# Controler.net
KiCad netlist of a schematic drawn in Altium Designer
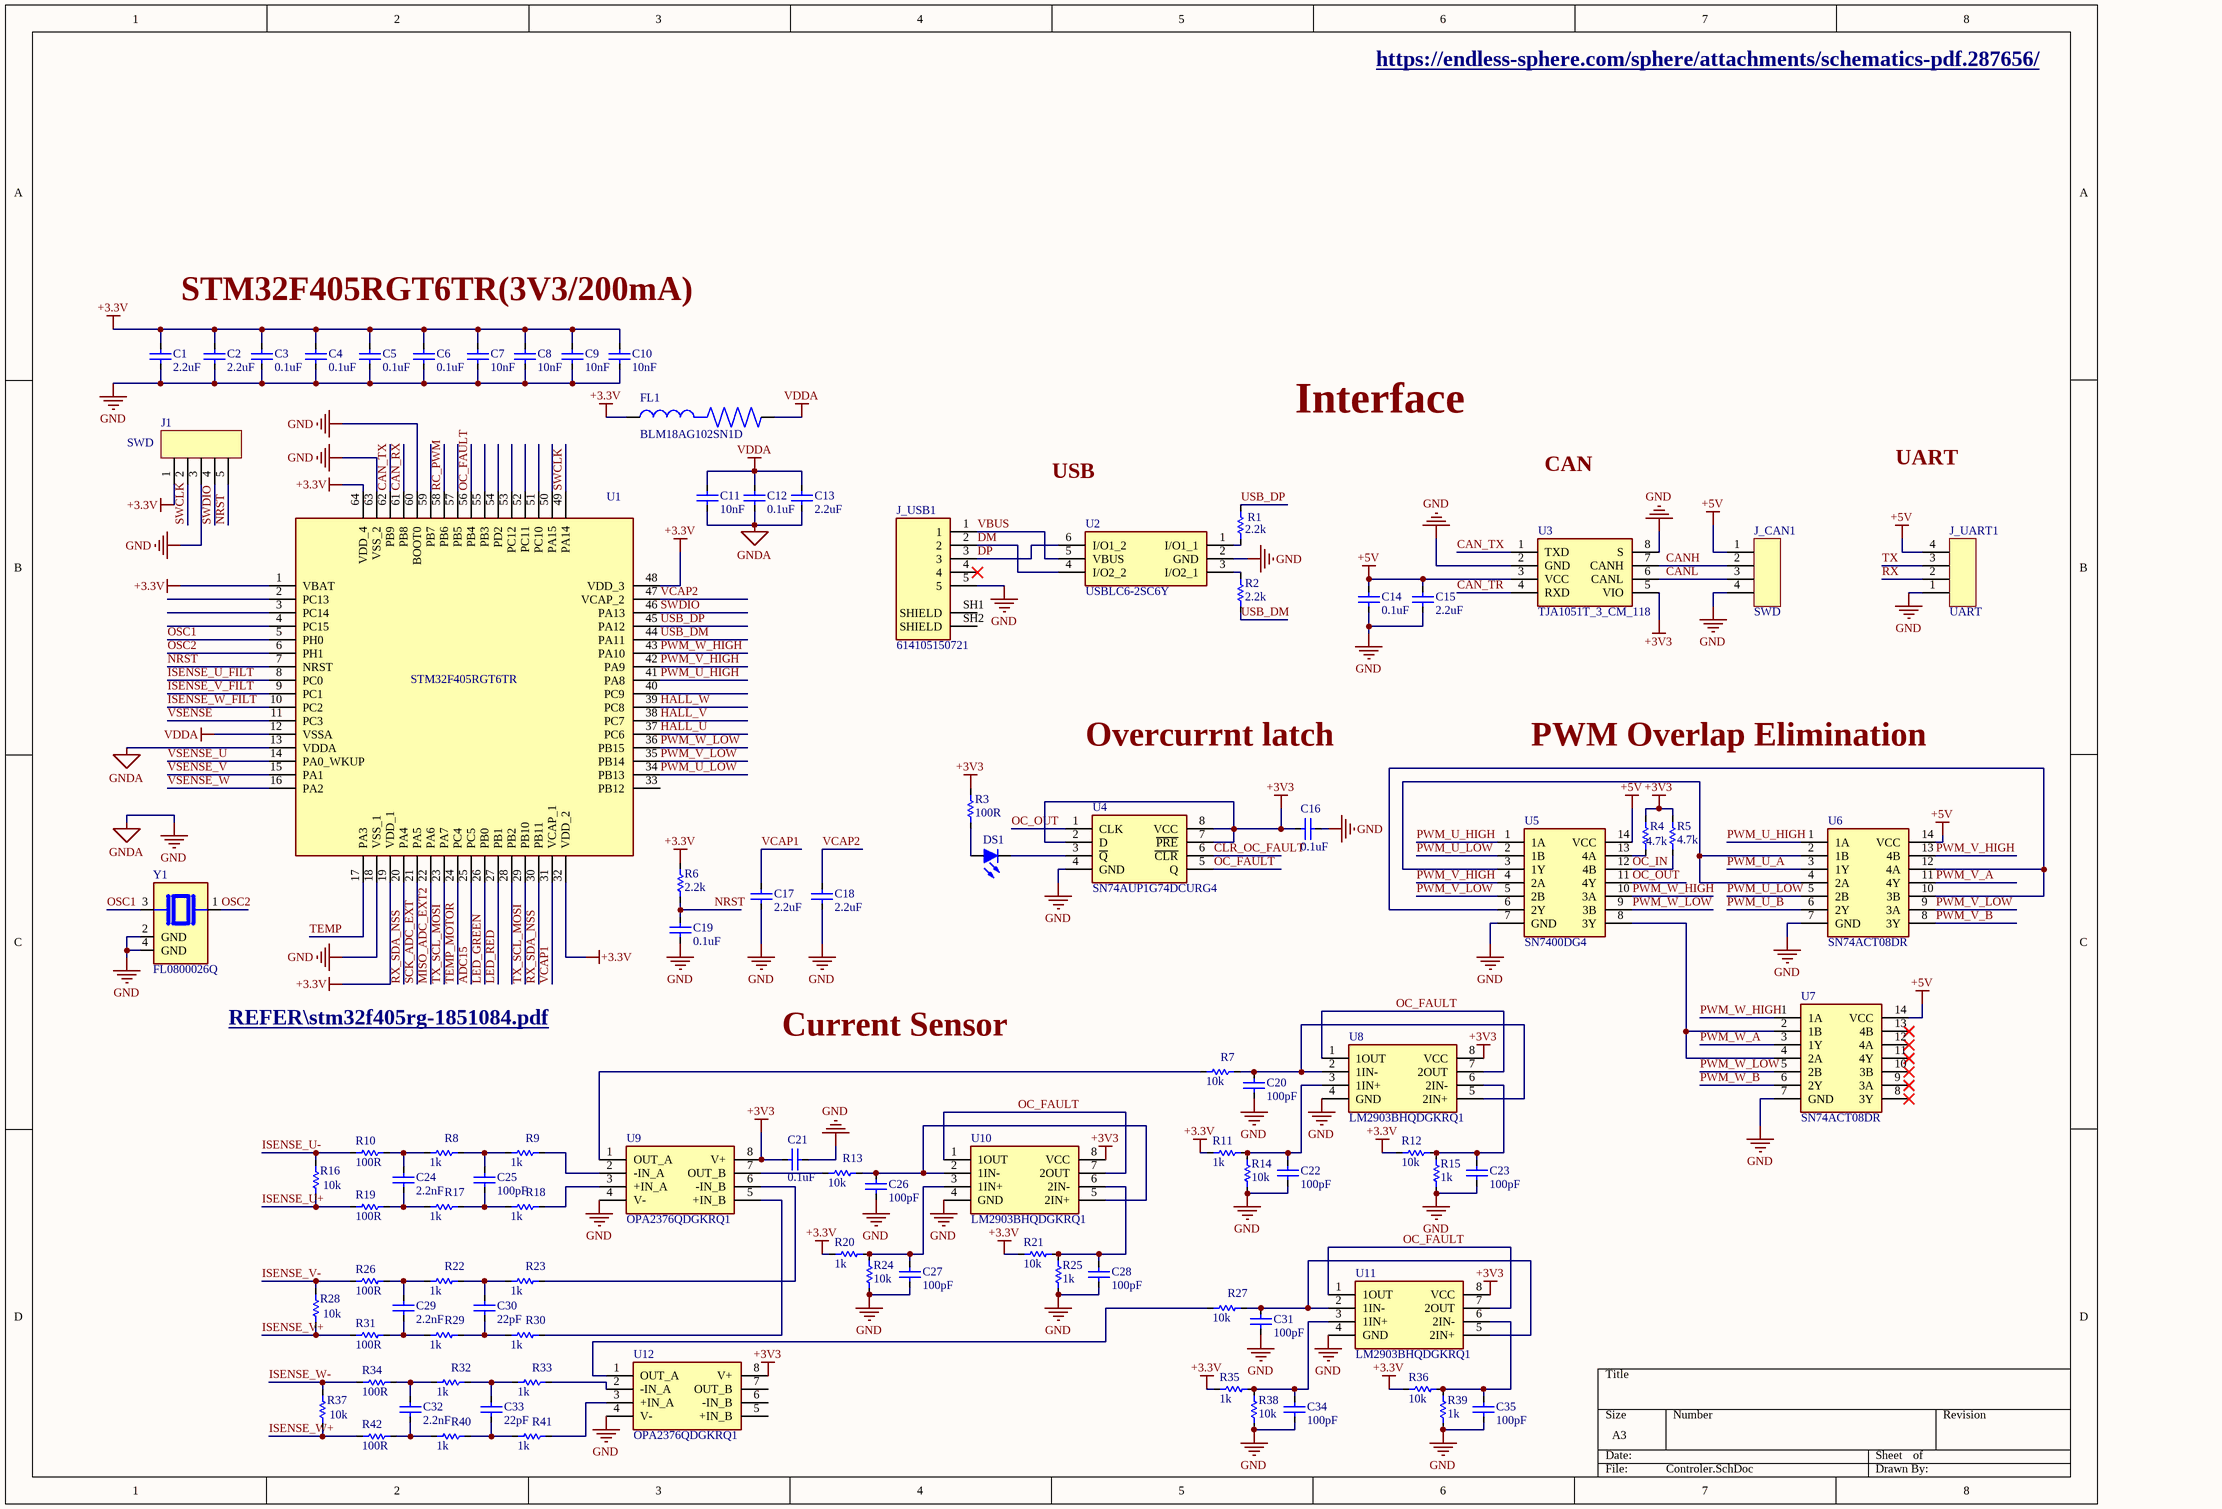
[diagram p0: Controler.SchDoc]

(export (version "E")
  (design (tool "Eeschema 10.0.6"))
  (components
    (comp (ref "C1")
      (value "2.2uF")
      (footprint "SMD_C(0603)")
      (description "PHE840MA6100MA04R17")
      (fields
        (field (name "MANUFACTURER") "Yageo")
        (field (name "MANUFACTURER PART NUMBER") "CC0603KPX7R9BB104")
      )
      (libsource (lib "CameraBoard") (part "Cap_9"))
    )
    (comp (ref "C2")
      (value "2.2uF")
      (footprint "SMD_C(0603)")
      (description "PHE840MA6100MA04R17")
      (fields
        (field (name "MANUFACTURER") "Yageo")
        (field (name "MANUFACTURER PART NUMBER") "CC0603KPX7R9BB104")
      )
      (libsource (lib "CameraBoard") (part "Cap_9"))
    )
    (comp (ref "C3")
      (value "0.1uF")
      (footprint "SMD_C(0402)")
      (description "Multilayer Ceramic Capacitors MLCC - SMD/SMT 50 V 0.1uF X7R 0603 10%")
      (fields
        (field (name "MANUFACTURER") "Yageo")
        (field (name "MANUFACTURER PART NUMBER") "CC0603KPX7R9BB104")
      )
      (libsource (lib "CameraBoard") (part "Cap_1"))
    )
    (comp (ref "C4")
      (value "0.1uF")
      (footprint "SMD_C(0402)")
      (description "Multilayer Ceramic Capacitors MLCC - SMD/SMT 50 V 0.1uF X7R 0603 10%")
      (fields
        (field (name "MANUFACTURER") "Yageo")
        (field (name "MANUFACTURER PART NUMBER") "CC0603KPX7R9BB104")
      )
      (libsource (lib "CameraBoard") (part "Cap_1"))
    )
    (comp (ref "C5")
      (value "0.1uF")
      (footprint "SMD_C(0402)")
      (description "Multilayer Ceramic Capacitors MLCC - SMD/SMT 50 V 0.1uF X7R 0603 10%")
      (fields
        (field (name "MANUFACTURER") "Yageo")
        (field (name "MANUFACTURER PART NUMBER") "CC0603KPX7R9BB104")
      )
      (libsource (lib "CameraBoard") (part "Cap_1"))
    )
    (comp (ref "C6")
      (value "0.1uF")
      (footprint "SMD_C(0402)")
      (description "Multilayer Ceramic Capacitors MLCC - SMD/SMT 50 V 0.1uF X7R 0603 10%")
      (fields
        (field (name "MANUFACTURER") "Yageo")
        (field (name "MANUFACTURER PART NUMBER") "CC0603KPX7R9BB104")
      )
      (libsource (lib "CameraBoard") (part "Cap_1"))
    )
    (comp (ref "C7")
      (value "10nF")
      (footprint "SMD_C(0402)")
      (description "Multilayer Ceramic Capacitors MLCC - SMD/SMT 50 V 10nF X7R 0603 10%")
      (fields
        (field (name "MANUFACTURER") "Yageo")
        (field (name "MANUFACTURER PART NUMBER") "CC0603KPX7R9BB103")
      )
      (libsource (lib "CameraBoard") (part "Cap_2"))
    )
    (comp (ref "C8")
      (value "10nF")
      (footprint "SMD_C(0402)")
      (description "Multilayer Ceramic Capacitors MLCC - SMD/SMT 50 V 10nF X7R 0603 10%")
      (fields
        (field (name "MANUFACTURER") "Yageo")
        (field (name "MANUFACTURER PART NUMBER") "CC0603KPX7R9BB103")
      )
      (libsource (lib "CameraBoard") (part "Cap_2"))
    )
    (comp (ref "C9")
      (value "10nF")
      (footprint "SMD_C(0402)")
      (description "Multilayer Ceramic Capacitors MLCC - SMD/SMT 50 V 10nF X7R 0603 10%")
      (fields
        (field (name "MANUFACTURER") "Yageo")
        (field (name "MANUFACTURER PART NUMBER") "CC0603KPX7R9BB103")
      )
      (libsource (lib "CameraBoard") (part "Cap_2"))
    )
    (comp (ref "C10")
      (value "10nF")
      (footprint "SMD_C(0402)")
      (description "Multilayer Ceramic Capacitors MLCC - SMD/SMT 50 V 10nF X7R 0603 10%")
      (fields
        (field (name "MANUFACTURER") "Yageo")
        (field (name "MANUFACTURER PART NUMBER") "CC0603KPX7R9BB103")
      )
      (libsource (lib "CameraBoard") (part "Cap_2"))
    )
    (comp (ref "C11")
      (value "10nF")
      (footprint "SMD_C(0402)")
      (description "Multilayer Ceramic Capacitors MLCC - SMD/SMT 50 V 10nF X7R 0603 10%")
      (fields
        (field (name "MANUFACTURER") "Yageo")
        (field (name "MANUFACTURER PART NUMBER") "CC0603KPX7R9BB103")
      )
      (libsource (lib "CameraBoard") (part "Cap_2"))
    )
    (comp (ref "C12")
      (value "0.1uF")
      (footprint "SMD_C(0402)")
      (description "Multilayer Ceramic Capacitors MLCC - SMD/SMT 50 V 0.1uF X7R 0603 10%")
      (fields
        (field (name "MANUFACTURER") "Yageo")
        (field (name "MANUFACTURER PART NUMBER") "CC0603KPX7R9BB104")
      )
      (libsource (lib "CameraBoard") (part "Cap_1"))
    )
    (comp (ref "C13")
      (value "2.2uF")
      (footprint "SMD_C(0603)")
      (description "PHE840MA6100MA04R17")
      (fields
        (field (name "MANUFACTURER") "Yageo")
        (field (name "MANUFACTURER PART NUMBER") "CC0603KPX7R9BB104")
      )
      (libsource (lib "CameraBoard") (part "Cap_9"))
    )
    (comp (ref "C14")
      (value "0.1uF")
      (footprint "SMD_C(0402)")
      (description "Multilayer Ceramic Capacitors MLCC - SMD/SMT 50 V 0.1uF X7R 0603 10%")
      (fields
        (field (name "MANUFACTURER") "Yageo")
        (field (name "MANUFACTURER PART NUMBER") "CC0603KPX7R9BB104")
      )
      (libsource (lib "CameraBoard") (part "Cap_1"))
    )
    (comp (ref "C15")
      (value "2.2uF")
      (footprint "SMD_C(0603)")
      (description "Multilayer Ceramic Capacitors MLCC - SMD/SMT 2.2 uF 50 VDC 10% 1206 X7R AEC-Q200")
      (fields
        (field (name "MANUFACTURER") "Yageo")
        (field (name "MANUFACTURER PART NUMBER") "GCM31CR71H225KA55K")
      )
      (libsource (lib "CameraBoard") (part "Cap_4"))
    )
    (comp (ref "C16")
      (value "0.1uF")
      (footprint "SMD_C(0402)")
      (description "Multilayer Ceramic Capacitors MLCC - SMD/SMT 50 V 0.1uF X7R 0603 10%")
      (fields
        (field (name "MANUFACTURER") "Yageo")
        (field (name "MANUFACTURER PART NUMBER") "CC0603KPX7R9BB104")
      )
      (libsource (lib "CameraBoard") (part "Cap_1"))
    )
    (comp (ref "C17")
      (value "2.2uF")
      (footprint "SMD_C(0603)")
      (description "Multilayer Ceramic Capacitors MLCC - SMD/SMT 2.2 uF 50 VDC 10% 1206 X7R AEC-Q200")
      (fields
        (field (name "MANUFACTURER") "Yageo")
        (field (name "MANUFACTURER PART NUMBER") "GCM31CR71H225KA55K")
      )
      (libsource (lib "CameraBoard") (part "Cap_4"))
    )
    (comp (ref "C18")
      (value "2.2uF")
      (footprint "SMD_C(0603)")
      (description "Multilayer Ceramic Capacitors MLCC - SMD/SMT 2.2 uF 50 VDC 10% 1206 X7R AEC-Q200")
      (fields
        (field (name "MANUFACTURER") "Yageo")
        (field (name "MANUFACTURER PART NUMBER") "GCM31CR71H225KA55K")
      )
      (libsource (lib "CameraBoard") (part "Cap_4"))
    )
    (comp (ref "C19")
      (value "0.1uF")
      (footprint "SMD_C(0402)")
      (description "Multilayer Ceramic Capacitors MLCC - SMD/SMT 50 V 0.1uF X7R 0603 10%")
      (fields
        (field (name "MANUFACTURER") "Yageo")
        (field (name "MANUFACTURER PART NUMBER") "CC0603KPX7R9BB104")
      )
      (libsource (lib "CameraBoard") (part "Cap_1"))
    )
    (comp (ref "C20")
      (value "100pF")
      (footprint "SMD_C(0402)")
      (description "PHE840MA6100MA04R17")
      (fields
        (field (name "MANUFACTURER") "Yageo")
        (field (name "MANUFACTURER PART NUMBER") "CC0603KPX7R9BB104")
      )
      (libsource (lib "CameraBoard") (part "Cap_7"))
    )
    (comp (ref "C21")
      (value "0.1uF")
      (footprint "SMD_C(0402)")
      (description "Multilayer Ceramic Capacitors MLCC - SMD/SMT 50 V 0.1uF X7R 0603 10%")
      (fields
        (field (name "MANUFACTURER") "Yageo")
        (field (name "MANUFACTURER PART NUMBER") "CC0603KPX7R9BB104")
      )
      (libsource (lib "CameraBoard") (part "Cap_1"))
    )
    (comp (ref "C22")
      (value "100pF")
      (footprint "SMD_C(0402)")
      (description "PHE840MA6100MA04R17")
      (fields
        (field (name "MANUFACTURER") "Yageo")
        (field (name "MANUFACTURER PART NUMBER") "CC0603KPX7R9BB104")
      )
      (libsource (lib "CameraBoard") (part "Cap_7"))
    )
    (comp (ref "C23")
      (value "100pF")
      (footprint "SMD_C(0402)")
      (description "PHE840MA6100MA04R17")
      (fields
        (field (name "MANUFACTURER") "Yageo")
        (field (name "MANUFACTURER PART NUMBER") "CC0603KPX7R9BB104")
      )
      (libsource (lib "CameraBoard") (part "Cap_7"))
    )
    (comp (ref "C24")
      (value "2.2nF")
      (footprint "SMD_C(0402)")
      (description "PHE840MA6100MA04R17")
      (fields
        (field (name "MANUFACTURER") "Yageo")
        (field (name "MANUFACTURER PART NUMBER") "CC0603KPX7R9BB104")
      )
      (libsource (lib "CameraBoard") (part "Cap_7"))
    )
    (comp (ref "C25")
      (value "100pF")
      (footprint "SMD_C(0402)")
      (description "PHE840MA6100MA04R17")
      (fields
        (field (name "MANUFACTURER") "Yageo")
        (field (name "MANUFACTURER PART NUMBER") "CC0603KPX7R9BB104")
      )
      (libsource (lib "CameraBoard") (part "Cap_7"))
    )
    (comp (ref "C26")
      (value "100pF")
      (footprint "SMD_C(0402)")
      (description "PHE840MA6100MA04R17")
      (fields
        (field (name "MANUFACTURER") "Yageo")
        (field (name "MANUFACTURER PART NUMBER") "CC0603KPX7R9BB104")
      )
      (libsource (lib "CameraBoard") (part "Cap_7"))
    )
    (comp (ref "C27")
      (value "100pF")
      (footprint "SMD_C(0402)")
      (description "PHE840MA6100MA04R17")
      (fields
        (field (name "MANUFACTURER") "Yageo")
        (field (name "MANUFACTURER PART NUMBER") "CC0603KPX7R9BB104")
      )
      (libsource (lib "CameraBoard") (part "Cap_7"))
    )
    (comp (ref "C28")
      (value "100pF")
      (footprint "SMD_C(0402)")
      (description "PHE840MA6100MA04R17")
      (fields
        (field (name "MANUFACTURER") "Yageo")
        (field (name "MANUFACTURER PART NUMBER") "CC0603KPX7R9BB104")
      )
      (libsource (lib "CameraBoard") (part "Cap_7"))
    )
    (comp (ref "C29")
      (value "2.2nF")
      (footprint "SMD_C(0402)")
      (description "PHE840MA6100MA04R17")
      (fields
        (field (name "MANUFACTURER") "Yageo")
        (field (name "MANUFACTURER PART NUMBER") "CC0603KPX7R9BB104")
      )
      (libsource (lib "CameraBoard") (part "Cap_7"))
    )
    (comp (ref "C30")
      (value "22pF")
      (footprint "SMD_C(0402)")
      (description "PHE840MA6100MA04R17")
      (fields
        (field (name "MANUFACTURER") "Yageo")
        (field (name "MANUFACTURER PART NUMBER") "CC0603KPX7R9BB104")
      )
      (libsource (lib "CameraBoard") (part "Cap_7"))
    )
    (comp (ref "C31")
      (value "100pF")
      (footprint "SMD_C(0402)")
      (description "PHE840MA6100MA04R17")
      (fields
        (field (name "MANUFACTURER") "Yageo")
        (field (name "MANUFACTURER PART NUMBER") "CC0603KPX7R9BB104")
      )
      (libsource (lib "CameraBoard") (part "Cap_7"))
    )
    (comp (ref "C32")
      (value "2.2nF")
      (footprint "SMD_C(0402)")
      (description "PHE840MA6100MA04R17")
      (fields
        (field (name "MANUFACTURER") "Yageo")
        (field (name "MANUFACTURER PART NUMBER") "CC0603KPX7R9BB104")
      )
      (libsource (lib "CameraBoard") (part "Cap_7"))
    )
    (comp (ref "C33")
      (value "22pF")
      (footprint "SMD_C(0402)")
      (description "PHE840MA6100MA04R17")
      (fields
        (field (name "MANUFACTURER") "Yageo")
        (field (name "MANUFACTURER PART NUMBER") "CC0603KPX7R9BB104")
      )
      (libsource (lib "CameraBoard") (part "Cap_7"))
    )
    (comp (ref "C34")
      (value "100pF")
      (footprint "SMD_C(0402)")
      (description "PHE840MA6100MA04R17")
      (fields
        (field (name "MANUFACTURER") "Yageo")
        (field (name "MANUFACTURER PART NUMBER") "CC0603KPX7R9BB104")
      )
      (libsource (lib "CameraBoard") (part "Cap_7"))
    )
    (comp (ref "C35")
      (value "100pF")
      (footprint "SMD_C(0402)")
      (description "PHE840MA6100MA04R17")
      (fields
        (field (name "MANUFACTURER") "Yageo")
        (field (name "MANUFACTURER PART NUMBER") "CC0603KPX7R9BB104")
      )
      (libsource (lib "CameraBoard") (part "Cap_7"))
    )
    (comp (ref "DS1")
      (value "SML-D12U1WT86")
      (footprint "LED0603")
      (description "Typical RED GaAs LED")
      (fields (field (name "MANUFACTURER") "Rohm Semiconductor"))
      (libsource (lib "Humidity Regulator") (part "SML-D12U1WT86"))
    )
    (comp (ref "FL1")
      (value "BLM18AG102SN1D")
      (footprint "BEADC1608X95N")
      (description "1 kOhms @ 100MHz 1 Ferrite Bead 0603 _1608 Metric_ 400mA 500mOhm")
      (fields (field (name "MF") "Murata") (field (name "DIGI-KEY_PART_NUMBER") "490-1015-1-ND"))
      (libsource (lib "BLM18AG102SN1D") (part "BLM18AG102SN1D"))
    )
    (comp (ref "J1")
      (value "SWD")
      (footprint "Header-2.54m-5pin")
      (description "5PinConnector")
      (libsource (lib "VESC_MotorController_3") (part "5PinConnector"))
    )
    (comp (ref "J_CAN1")
      (value "SWD")
      (footprint "Header-2.54m-4pin")
      (description "4PinConnector")
      (libsource (lib "CameraBoard") (part "4PinConnector"))
    )
    (comp (ref "J_UART1")
      (value "UART")
      (footprint "Header-2.54m-4pin")
      (description "4PinConnector")
      (libsource (lib "") (part "4PinConnector_1"))
    )
    (comp (ref "J_USB1")
      (value "614105150721")
      (footprint "WURTH_614105150721")
      (description "USB - micro B USB 2.0 Receptacle Connector 5 Position Through Hole")
      (fields (field (name "DIGI-KEY_PART_NUMBER") "732-5958-1-ND") (field (name "MF") "Wurth Electronics"))
      (libsource (lib "614105150721") (part "614105150721"))
    )
    (comp (ref "R1")
      (value "2.2k")
      (footprint "SMD_R(0402)")
      (description "CRCW04024R02FKED")
      (fields (field (name "PUBLISHER") "Altium Limited"))
      (libsource (lib "CameraBoard") (part "Res Semi_2"))
    )
    (comp (ref "R2")
      (value "2.2k")
      (footprint "SMD_R(0402)")
      (description "CRCW04024R02FKED")
      (fields (field (name "PUBLISHER") "Altium Limited"))
      (libsource (lib "CameraBoard") (part "Res Semi_2"))
    )
    (comp (ref "R3")
      (value "100R")
      (footprint "SMD_R(0402)")
      (description "CRCW04024R02FKED")
      (fields (field (name "PUBLISHER") "Altium Limited"))
      (libsource (lib "CameraBoard") (part "Res Semi_1"))
    )
    (comp (ref "R4")
      (value "4.7k")
      (footprint "SMD_R(0402)")
      (description "CRCW04024R02FKED")
      (fields (field (name "PUBLISHER") "Altium Limited"))
      (libsource (lib "CameraBoard") (part "Res Semi_3"))
    )
    (comp (ref "R5")
      (value "4.7k")
      (footprint "SMD_R(0402)")
      (description "CRCW04024R02FKED")
      (fields (field (name "PUBLISHER") "Altium Limited"))
      (libsource (lib "CameraBoard") (part "Res Semi_3"))
    )
    (comp (ref "R6")
      (value "2.2k")
      (footprint "SMD_R(0402)")
      (description "CRCW04024R02FKED")
      (fields (field (name "PUBLISHER") "Altium Limited"))
      (libsource (lib "CameraBoard") (part "Res Semi_2"))
    )
    (comp (ref "R7")
      (value "10k")
      (footprint "SMD_R(0402)")
      (description "CRCW04024R02FKED")
      (fields (field (name "PUBLISHER") "Altium Limited"))
      (libsource (lib "CameraBoard") (part "Res Semi_1"))
    )
    (comp (ref "R8")
      (value "1k")
      (footprint "SMD_R(0402)")
      (description "CRCW04024R02FKED")
      (fields (field (name "PUBLISHER") "Altium Limited"))
      (libsource (lib "CameraBoard") (part "Res Semi_1"))
    )
    (comp (ref "R9")
      (value "1k")
      (footprint "SMD_R(0402)")
      (description "CRCW04024R02FKED")
      (fields (field (name "PUBLISHER") "Altium Limited"))
      (libsource (lib "CameraBoard") (part "Res Semi_1"))
    )
    (comp (ref "R10")
      (value "100R")
      (footprint "SMD_R(0402)")
      (description "CRCW04024R02FKED")
      (fields (field (name "PUBLISHER") "Altium Limited"))
      (libsource (lib "CameraBoard") (part "Res Semi_1"))
    )
    (comp (ref "R11")
      (value "1k")
      (footprint "SMD_R(0402)")
      (description "CRCW04024R02FKED")
      (fields (field (name "PUBLISHER") "Altium Limited"))
      (libsource (lib "CameraBoard") (part "Res Semi_1"))
    )
    (comp (ref "R12")
      (value "10k")
      (footprint "SMD_R(0402)")
      (description "CRCW04024R02FKED")
      (fields (field (name "PUBLISHER") "Altium Limited"))
      (libsource (lib "CameraBoard") (part "Res Semi_1"))
    )
    (comp (ref "R13")
      (value "10k")
      (footprint "SMD_R(0402)")
      (description "CRCW04024R02FKED")
      (fields (field (name "PUBLISHER") "Altium Limited"))
      (libsource (lib "CameraBoard") (part "Res Semi_1"))
    )
    (comp (ref "R14")
      (value "10k")
      (footprint "SMD_R(0402)")
      (description "CRCW04024R02FKED")
      (fields (field (name "PUBLISHER") "Altium Limited"))
      (libsource (lib "CameraBoard") (part "Res Semi_1"))
    )
    (comp (ref "R15")
      (value "1k")
      (footprint "SMD_R(0402)")
      (description "CRCW04024R02FKED")
      (fields (field (name "PUBLISHER") "Altium Limited"))
      (libsource (lib "CameraBoard") (part "Res Semi_1"))
    )
    (comp (ref "R16")
      (value "10k")
      (footprint "SMD_R(0402)")
      (description "CRCW04024R02FKED")
      (fields (field (name "PUBLISHER") "Altium Limited"))
      (libsource (lib "CameraBoard") (part "Res Semi_1"))
    )
    (comp (ref "R17")
      (value "1k")
      (footprint "SMD_R(0402)")
      (description "CRCW04024R02FKED")
      (fields (field (name "PUBLISHER") "Altium Limited"))
      (libsource (lib "CameraBoard") (part "Res Semi_1"))
    )
    (comp (ref "R18")
      (value "1k")
      (footprint "SMD_R(0402)")
      (description "CRCW04024R02FKED")
      (fields (field (name "PUBLISHER") "Altium Limited"))
      (libsource (lib "CameraBoard") (part "Res Semi_1"))
    )
    (comp (ref "R19")
      (value "100R")
      (footprint "SMD_R(0402)")
      (description "CRCW04024R02FKED")
      (fields (field (name "PUBLISHER") "Altium Limited"))
      (libsource (lib "CameraBoard") (part "Res Semi_1"))
    )
    (comp (ref "R20")
      (value "1k")
      (footprint "SMD_R(0402)")
      (description "CRCW04024R02FKED")
      (fields (field (name "PUBLISHER") "Altium Limited"))
      (libsource (lib "CameraBoard") (part "Res Semi_1"))
    )
    (comp (ref "R21")
      (value "10k")
      (footprint "SMD_R(0402)")
      (description "CRCW04024R02FKED")
      (fields (field (name "PUBLISHER") "Altium Limited"))
      (libsource (lib "CameraBoard") (part "Res Semi_1"))
    )
    (comp (ref "R22")
      (value "1k")
      (footprint "SMD_R(0402)")
      (description "CRCW04024R02FKED")
      (fields (field (name "PUBLISHER") "Altium Limited"))
      (libsource (lib "CameraBoard") (part "Res Semi_1"))
    )
    (comp (ref "R23")
      (value "1k")
      (footprint "SMD_R(0402)")
      (description "CRCW04024R02FKED")
      (fields (field (name "PUBLISHER") "Altium Limited"))
      (libsource (lib "CameraBoard") (part "Res Semi_1"))
    )
    (comp (ref "R24")
      (value "10k")
      (footprint "SMD_R(0402)")
      (description "CRCW04024R02FKED")
      (fields (field (name "PUBLISHER") "Altium Limited"))
      (libsource (lib "CameraBoard") (part "Res Semi_1"))
    )
    (comp (ref "R25")
      (value "1k")
      (footprint "SMD_R(0402)")
      (description "CRCW04024R02FKED")
      (fields (field (name "PUBLISHER") "Altium Limited"))
      (libsource (lib "CameraBoard") (part "Res Semi_1"))
    )
    (comp (ref "R26")
      (value "100R")
      (footprint "SMD_R(0402)")
      (description "CRCW04024R02FKED")
      (fields (field (name "PUBLISHER") "Altium Limited"))
      (libsource (lib "CameraBoard") (part "Res Semi_1"))
    )
    (comp (ref "R27")
      (value "10k")
      (footprint "SMD_R(0402)")
      (description "CRCW04024R02FKED")
      (fields (field (name "PUBLISHER") "Altium Limited"))
      (libsource (lib "CameraBoard") (part "Res Semi_1"))
    )
    (comp (ref "R28")
      (value "10k")
      (footprint "SMD_R(0402)")
      (description "CRCW04024R02FKED")
      (fields (field (name "PUBLISHER") "Altium Limited"))
      (libsource (lib "CameraBoard") (part "Res Semi_1"))
    )
    (comp (ref "R29")
      (value "1k")
      (footprint "SMD_R(0402)")
      (description "CRCW04024R02FKED")
      (fields (field (name "PUBLISHER") "Altium Limited"))
      (libsource (lib "CameraBoard") (part "Res Semi_1"))
    )
    (comp (ref "R30")
      (value "1k")
      (footprint "SMD_R(0402)")
      (description "CRCW04024R02FKED")
      (fields (field (name "PUBLISHER") "Altium Limited"))
      (libsource (lib "CameraBoard") (part "Res Semi_1"))
    )
    (comp (ref "R31")
      (value "100R")
      (footprint "SMD_R(0402)")
      (description "CRCW04024R02FKED")
      (fields (field (name "PUBLISHER") "Altium Limited"))
      (libsource (lib "CameraBoard") (part "Res Semi_1"))
    )
    (comp (ref "R32")
      (value "1k")
      (footprint "SMD_R(0402)")
      (description "CRCW04024R02FKED")
      (fields (field (name "PUBLISHER") "Altium Limited"))
      (libsource (lib "CameraBoard") (part "Res Semi_1"))
    )
    (comp (ref "R33")
      (value "1k")
      (footprint "SMD_R(0402)")
      (description "CRCW04024R02FKED")
      (fields (field (name "PUBLISHER") "Altium Limited"))
      (libsource (lib "CameraBoard") (part "Res Semi_1"))
    )
    (comp (ref "R34")
      (value "100R")
      (footprint "SMD_R(0402)")
      (description "CRCW04024R02FKED")
      (fields (field (name "PUBLISHER") "Altium Limited"))
      (libsource (lib "CameraBoard") (part "Res Semi_1"))
    )
    (comp (ref "R35")
      (value "1k")
      (footprint "SMD_R(0402)")
      (description "CRCW04024R02FKED")
      (fields (field (name "PUBLISHER") "Altium Limited"))
      (libsource (lib "CameraBoard") (part "Res Semi_1"))
    )
    (comp (ref "R36")
      (value "10k")
      (footprint "SMD_R(0402)")
      (description "CRCW04024R02FKED")
      (fields (field (name "PUBLISHER") "Altium Limited"))
      (libsource (lib "CameraBoard") (part "Res Semi_1"))
    )
    (comp (ref "R37")
      (value "10k")
      (footprint "SMD_R(0402)")
      (description "CRCW04024R02FKED")
      (fields (field (name "PUBLISHER") "Altium Limited"))
      (libsource (lib "CameraBoard") (part "Res Semi_1"))
    )
    (comp (ref "R38")
      (value "10k")
      (footprint "SMD_R(0402)")
      (description "CRCW04024R02FKED")
      (fields (field (name "PUBLISHER") "Altium Limited"))
      (libsource (lib "CameraBoard") (part "Res Semi_1"))
    )
    (comp (ref "R39")
      (value "1k")
      (footprint "SMD_R(0402)")
      (description "CRCW04024R02FKED")
      (fields (field (name "PUBLISHER") "Altium Limited"))
      (libsource (lib "CameraBoard") (part "Res Semi_1"))
    )
    (comp (ref "R40")
      (value "1k")
      (footprint "SMD_R(0402)")
      (description "CRCW04024R02FKED")
      (fields (field (name "PUBLISHER") "Altium Limited"))
      (libsource (lib "CameraBoard") (part "Res Semi_1"))
    )
    (comp (ref "R41")
      (value "1k")
      (footprint "SMD_R(0402)")
      (description "CRCW04024R02FKED")
      (fields (field (name "PUBLISHER") "Altium Limited"))
      (libsource (lib "CameraBoard") (part "Res Semi_1"))
    )
    (comp (ref "R42")
      (value "100R")
      (footprint "SMD_R(0402)")
      (description "CRCW04024R02FKED")
      (fields (field (name "PUBLISHER") "Altium Limited"))
      (libsource (lib "CameraBoard") (part "Res Semi_1"))
    )
    (comp (ref "U1")
      (value "STM32F405RGT6TR")
      (footprint "QFP50P1200X1200X160-64N")
      (fields (field (name "MOUSER PART NUMBER") "511-STM32F405RGT6TR"))
      (libsource (lib "STM32F405RGT6TR") (part "STM32F405RGT6TR"))
    )
    (comp (ref "U2")
      (value "USBLC6-2SC6Y")
      (footprint "SOT95P280X145-6N")
      (fields (field (name "MOUSER PART NUMBER") "511-USBLC6-2SC6Y"))
      (libsource (lib "USBLC6-2SC6Y") (part "USBLC6-2SC6Y"))
    )
    (comp (ref "U3")
      (value "TJA1051T_3_CM_118")
      (footprint "SOIC127P600X175-8N")
      (description "CAN Interface IC BL Advanced Automotive Analog")
      (fields
        (field (name "MOUSER PART NUMBER") "771-TJA1051T/3CM118")
        (field (name "MANUFACTURER_PART_NUMBER") "TJA1051T/3/CM,118")
      )
      (libsource (lib "TJA1051T_3_CM_118") (part "TJA1051T_3_CM_118"))
    )
    (comp (ref "U4")
      (value "SN74AUP1G74DCURG4")
      (footprint "SOP50P310X90-8N")
      (description "Flip Flops Lo PWR SNGL Pos Edge Trgrd DType FlipFlop")
      (fields (field (name "MOUSER PART NUMBER") "595-74AUP1G74DCURG4"))
      (libsource (lib "SN74AUP1G74DCURG4") (part "SN74AUP1G74DCURG4"))
    )
    (comp (ref "U5")
      (value "SN7400DG4")
      (footprint "SOIC127P600X175-14N")
      (description "NAND Gate 4-Element 2-IN Bipolar 14-Pin SOIC Tube")
      (fields (field (name "MOUSER PART NUMBER") "595-SN7400DG4"))
      (libsource (lib "SN7400DG4") (part "SN7400DG4"))
    )
    (comp (ref "U6")
      (value "SN74ACT08DR")
      (footprint "SOIC127P600X175-14N")
      (description "Texas Instruments SN74ACT08DR, AND Quad 2 Input AND, 4.5  5.5 V, 14-Pin SOIC")
      (fields (field (name "MOUSER PART NUMBER") "595-SN74ACT08DR"))
      (libsource (lib "SN74ACT08DR") (part "SN74ACT08DR"))
    )
    (comp (ref "U7")
      (value "SN74ACT08DR")
      (footprint "SOIC127P600X175-14N")
      (description "Texas Instruments SN74ACT08DR, AND Quad 2 Input AND, 4.5  5.5 V, 14-Pin SOIC")
      (fields (field (name "MOUSER PART NUMBER") "595-SN74ACT08DR"))
      (libsource (lib "SN74ACT08DR") (part "SN74ACT08DR"))
    )
    (comp (ref "U8")
      (value "LM2903BHQDGKRQ1")
      (footprint "SOP65P490X110-8N")
      (description "Analog Comparators Automotive, dual, differential, commodity comparator")
      (fields (field (name "MOUSER PART NUMBER") "595-LM2903BHQDGKRQ1"))
      (libsource (lib "LM2903BHQDGKRQ1") (part "LM2903BHQDGKRQ1"))
    )
    (comp (ref "U9")
      (value "OPA2376QDGKRQ1")
      (footprint "SOP65P490X110-8N")
      (description "Low Noise, Low Quiescent Current, Precision Operational Amplifier e-trim/trade")
      (fields (field (name "MOUSER PART NUMBER") "595-OPA2376QDGKRQ1"))
      (libsource (lib "OPA2376QDGKRQ1") (part "OPA2376QDGKRQ1"))
    )
    (comp (ref "U10")
      (value "LM2903BHQDGKRQ1")
      (footprint "SOP65P490X110-8N")
      (description "Analog Comparators Automotive, dual, differential, commodity comparator")
      (fields (field (name "MOUSER PART NUMBER") "595-LM2903BHQDGKRQ1"))
      (libsource (lib "LM2903BHQDGKRQ1") (part "LM2903BHQDGKRQ1"))
    )
    (comp (ref "U11")
      (value "LM2903BHQDGKRQ1")
      (footprint "SOP65P490X110-8N")
      (description "Analog Comparators Automotive, dual, differential, commodity comparator")
      (fields (field (name "MOUSER PART NUMBER") "595-LM2903BHQDGKRQ1"))
      (libsource (lib "LM2903BHQDGKRQ1") (part "LM2903BHQDGKRQ1"))
    )
    (comp (ref "U12")
      (value "OPA2376QDGKRQ1")
      (footprint "SOP65P490X110-8N")
      (description "Low Noise, Low Quiescent Current, Precision Operational Amplifier e-trim/trade")
      (fields (field (name "MOUSER PART NUMBER") "595-OPA2376QDGKRQ1"))
      (libsource (lib "OPA2376QDGKRQ1") (part "OPA2376QDGKRQ1"))
    )
    (comp (ref "Y1")
      (value "FL0800026Q")
      (footprint "XTAL_FL0800026Q")
      (description "8 MHz Â±30ppm Crystal 8pF 400 Ohms 4-SMD, No Lead")
      (fields (field (name "MF") "Diodes Incorporated"))
      (libsource (lib "FL0800026Q") (part "FL0800026Q"))
    )
  )
  (nets
    (net (code "1") (name "+3.3V") (class "Default")
      (node (ref "C1") (pin "2") (pinfunction "2_2") (pintype "passive"))
      (node (ref "C10") (pin "2") (pinfunction "2_2") (pintype "passive"))
      (node (ref "C2") (pin "2") (pinfunction "2_2") (pintype "passive"))
      (node (ref "C3") (pin "2") (pinfunction "2_2") (pintype "passive"))
      (node (ref "C4") (pin "2") (pinfunction "2_2") (pintype "passive"))
      (node (ref "C5") (pin "2") (pinfunction "2_2") (pintype "passive"))
      (node (ref "C6") (pin "2") (pinfunction "2_2") (pintype "passive"))
      (node (ref "C7") (pin "2") (pinfunction "2_2") (pintype "passive"))
      (node (ref "C8") (pin "2") (pinfunction "2_2") (pintype "passive"))
      (node (ref "C9") (pin "2") (pinfunction "2_2") (pintype "passive"))
      (node (ref "FL1") (pin "1") (pinfunction "1_1") (pintype "passive"))
      (node (ref "J1") (pin "1") (pinfunction "1_1") (pintype "passive"))
      (node (ref "R11") (pin "1") (pinfunction "1_1") (pintype "passive"))
      (node (ref "R12") (pin "1") (pinfunction "1_1") (pintype "passive"))
      (node (ref "R20") (pin "1") (pinfunction "1_1") (pintype "passive"))
      (node (ref "R21") (pin "1") (pinfunction "1_1") (pintype "passive"))
      (node (ref "R35") (pin "1") (pinfunction "1_1") (pintype "passive"))
      (node (ref "R36") (pin "1") (pinfunction "1_1") (pintype "passive"))
      (node (ref "R6") (pin "2") (pinfunction "2_2") (pintype "passive"))
      (node (ref "U1") (pin "1") (pinfunction "VBAT_1") (pintype "passive"))
      (node (ref "U1") (pin "19") (pinfunction "VDD_1_19") (pintype "passive"))
      (node (ref "U1") (pin "32") (pinfunction "VDD_2_32") (pintype "passive"))
      (node (ref "U1") (pin "48") (pinfunction "VDD_3_48") (pintype "passive"))
      (node (ref "U1") (pin "64") (pinfunction "VDD_4_64") (pintype "passive"))
    )
    (net (code "2") (name "+3V3") (class "Default")
      (node (ref "C16") (pin "2") (pinfunction "2_2") (pintype "passive"))
      (node (ref "C21") (pin "1") (pinfunction "1_1") (pintype "passive"))
      (node (ref "R3") (pin "2") (pinfunction "2_2") (pintype "passive"))
      (node (ref "R4") (pin "2") (pinfunction "2_2") (pintype "passive"))
      (node (ref "R5") (pin "2") (pinfunction "2_2") (pintype "passive"))
      (node (ref "U10") (pin "8") (pinfunction "VCC_8") (pintype "passive"))
      (node (ref "U11") (pin "8") (pinfunction "VCC_8") (pintype "passive"))
      (node (ref "U12") (pin "8") (pinfunction "V+_8") (pintype "passive"))
      (node (ref "U3") (pin "5") (pinfunction "VIO_5") (pintype "passive"))
      (node (ref "U4") (pin "2") (pinfunction "D_2") (pintype "passive"))
      (node (ref "U4") (pin "7") (pinfunction "~{PRE}_7") (pintype "passive"))
      (node (ref "U4") (pin "8") (pinfunction "VCC_8") (pintype "passive"))
      (node (ref "U8") (pin "8") (pinfunction "VCC_8") (pintype "passive"))
      (node (ref "U9") (pin "8") (pinfunction "V+_8") (pintype "passive"))
    )
    (net (code "3") (name "+5V") (class "Default")
      (node (ref "C14") (pin "2") (pinfunction "2_2") (pintype "passive"))
      (node (ref "C15") (pin "2") (pinfunction "2_2") (pintype "passive"))
      (node (ref "J_CAN1") (pin "1") (pinfunction "1_1") (pintype "passive"))
      (node (ref "J_UART1") (pin "4") (pinfunction "4_4") (pintype "passive"))
      (node (ref "U3") (pin "3") (pinfunction "VCC_3") (pintype "power_in"))
      (node (ref "U5") (pin "14") (pinfunction "VCC_14") (pintype "passive"))
      (node (ref "U6") (pin "14") (pinfunction "VCC_14") (pintype "passive"))
      (node (ref "U7") (pin "14") (pinfunction "VCC_14") (pintype "passive"))
    )
    (net (code "4") (name "/ADC15") (class "Default")
      (node (ref "U1") (pin "25") (pinfunction "PC5_25") (pintype "passive"))
    )
    (net (code "5") (name "/CANH") (class "Default")
      (node (ref "J_CAN1") (pin "2") (pinfunction "2_2") (pintype "passive"))
      (node (ref "U3") (pin "7") (pinfunction "CANH_7") (pintype "passive"))
    )
    (net (code "6") (name "/CANL") (class "Default")
      (node (ref "J_CAN1") (pin "3") (pinfunction "3_3") (pintype "passive"))
      (node (ref "U3") (pin "6") (pinfunction "CANL_6") (pintype "passive"))
    )
    (net (code "7") (name "/CAN_RX") (class "Default")
      (node (ref "U1") (pin "61") (pinfunction "PB8_61") (pintype "passive"))
    )
    (net (code "8") (name "/CAN_TR") (class "Default")
      (node (ref "U3") (pin "4") (pinfunction "RXD_4") (pintype "passive"))
    )
    (net (code "9") (name "/CAN_TX") (class "Default")
      (node (ref "U1") (pin "62") (pinfunction "PB9_62") (pintype "passive"))
      (node (ref "U3") (pin "1") (pinfunction "TXD_1") (pintype "passive"))
    )
    (net (code "10") (name "/CLR_OC_FAULT") (class "Default")
      (node (ref "U4") (pin "6") (pinfunction "~{CLR}_6") (pintype "passive"))
    )
    (net (code "11") (name "/DM") (class "Default")
      (node (ref "J_USB1") (pin "2") (pinfunction "2_2") (pintype "passive"))
      (node (ref "U2") (pin "4") (pinfunction "I/O2_2_4") (pintype "passive"))
    )
    (net (code "12") (name "/DP") (class "Default")
      (node (ref "J_USB1") (pin "3") (pinfunction "3_3") (pintype "passive"))
      (node (ref "U2") (pin "6") (pinfunction "I/O1_2_6") (pintype "passive"))
    )
    (net (code "13") (name "/HALL_U") (class "Default")
      (node (ref "U1") (pin "37") (pinfunction "PC6_37") (pintype "passive"))
    )
    (net (code "14") (name "/HALL_V") (class "Default")
      (node (ref "U1") (pin "38") (pinfunction "PC7_38") (pintype "passive"))
    )
    (net (code "15") (name "/HALL_W") (class "Default")
      (node (ref "U1") (pin "39") (pinfunction "PC8_39") (pintype "passive"))
    )
    (net (code "16") (name "/ISENSE_U+") (class "Default")
      (node (ref "R16") (pin "2") (pinfunction "2_2") (pintype "passive"))
      (node (ref "R19") (pin "2") (pinfunction "2_2") (pintype "passive"))
    )
    (net (code "17") (name "/ISENSE_U-") (class "Default")
      (node (ref "R10") (pin "2") (pinfunction "2_2") (pintype "passive"))
      (node (ref "R16") (pin "1") (pinfunction "1_1") (pintype "passive"))
    )
    (net (code "18") (name "/ISENSE_U_FILT") (class "Default")
      (node (ref "U1") (pin "8") (pinfunction "PC0_8") (pintype "passive"))
    )
    (net (code "19") (name "/ISENSE_V+") (class "Default")
      (node (ref "R28") (pin "2") (pinfunction "2_2") (pintype "passive"))
      (node (ref "R31") (pin "2") (pinfunction "2_2") (pintype "passive"))
    )
    (net (code "20") (name "/ISENSE_V-") (class "Default")
      (node (ref "R26") (pin "2") (pinfunction "2_2") (pintype "passive"))
      (node (ref "R28") (pin "1") (pinfunction "1_1") (pintype "passive"))
    )
    (net (code "21") (name "/ISENSE_V_FILT") (class "Default")
      (node (ref "U1") (pin "9") (pinfunction "PC1_9") (pintype "passive"))
    )
    (net (code "22") (name "/ISENSE_W+") (class "Default")
      (node (ref "R37") (pin "2") (pinfunction "2_2") (pintype "passive"))
      (node (ref "R42") (pin "2") (pinfunction "2_2") (pintype "passive"))
    )
    (net (code "23") (name "/ISENSE_W-") (class "Default")
      (node (ref "R34") (pin "2") (pinfunction "2_2") (pintype "passive"))
      (node (ref "R37") (pin "1") (pinfunction "1_1") (pintype "passive"))
    )
    (net (code "24") (name "/ISENSE_W_FILT") (class "Default")
      (node (ref "U1") (pin "10") (pinfunction "PC2_10") (pintype "passive"))
    )
    (net (code "25") (name "/LED_GREEN") (class "Default")
      (node (ref "U1") (pin "26") (pinfunction "PB0_26") (pintype "passive"))
    )
    (net (code "26") (name "/LED_RED") (class "Default")
      (node (ref "U1") (pin "27") (pinfunction "PB1_27") (pintype "passive"))
    )
    (net (code "27") (name "/MISO_ADC_EXT2") (class "Default")
      (node (ref "U1") (pin "22") (pinfunction "PA6_22") (pintype "passive"))
    )
    (net (code "28") (name "/NRST") (class "Default")
      (node (ref "C19") (pin "2") (pinfunction "2_2") (pintype "passive"))
      (node (ref "J1") (pin "5") (pinfunction "5_5") (pintype "passive"))
      (node (ref "R6") (pin "1") (pinfunction "1_1") (pintype "passive"))
      (node (ref "U1") (pin "7") (pinfunction "NRST_7") (pintype "passive"))
    )
    (net (code "29") (name "/OC_FAULT") (class "Default")
      (node (ref "U1") (pin "56") (pinfunction "PB4_56") (pintype "passive"))
      (node (ref "U10") (pin "1") (pinfunction "1OUT_1") (pintype "passive"))
      (node (ref "U10") (pin "7") (pinfunction "2OUT_7") (pintype "passive"))
      (node (ref "U11") (pin "1") (pinfunction "1OUT_1") (pintype "passive"))
      (node (ref "U11") (pin "7") (pinfunction "2OUT_7") (pintype "passive"))
      (node (ref "U4") (pin "5") (pinfunction "Q_5") (pintype "passive"))
      (node (ref "U8") (pin "1") (pinfunction "1OUT_1") (pintype "passive"))
      (node (ref "U8") (pin "7") (pinfunction "2OUT_7") (pintype "passive"))
    )
    (net (code "30") (name "/OC_IN") (class "Default")
      (node (ref "R5") (pin "1") (pinfunction "1_1") (pintype "passive"))
      (node (ref "U5") (pin "12") (pinfunction "4B_12") (pintype "passive"))
    )
    (net (code "31") (name "/OC_OUT") (class "Default")
      (node (ref "U4") (pin "1") (pinfunction "CLK_1") (pintype "passive"))
      (node (ref "U5") (pin "11") (pinfunction "4Y_11") (pintype "passive"))
    )
    (net (code "32") (name "/OSC1") (class "Default")
      (node (ref "U1") (pin "5") (pinfunction "PH0_5") (pintype "passive"))
      (node (ref "Y1") (pin "3") (pinfunction "2_3") (pintype "passive"))
    )
    (net (code "33") (name "/OSC2") (class "Default")
      (node (ref "U1") (pin "6") (pinfunction "PH1_6") (pintype "passive"))
      (node (ref "Y1") (pin "1") (pinfunction "1_1") (pintype "passive"))
    )
    (net (code "34") (name "/PWM_U_A") (class "Default")
      (node (ref "U6") (pin "3") (pinfunction "1Y_3") (pintype "passive"))
    )
    (net (code "35") (name "/PWM_U_B") (class "Default")
      (node (ref "U6") (pin "6") (pinfunction "2Y_6") (pintype "passive"))
    )
    (net (code "36") (name "/PWM_U_HIGH") (class "Default")
      (node (ref "U1") (pin "41") (pinfunction "PA8_41") (pintype "passive"))
      (node (ref "U5") (pin "1") (pinfunction "1A_1") (pintype "passive"))
      (node (ref "U6") (pin "1") (pinfunction "1A_1") (pintype "passive"))
    )
    (net (code "37") (name "/PWM_U_LOW") (class "Default")
      (node (ref "U1") (pin "34") (pinfunction "PB13_34") (pintype "passive"))
      (node (ref "U5") (pin "2") (pinfunction "1B_2") (pintype "passive"))
      (node (ref "U6") (pin "5") (pinfunction "2B_5") (pintype "passive"))
    )
    (net (code "38") (name "/PWM_V_A") (class "Default")
      (node (ref "U6") (pin "11") (pinfunction "4Y_11") (pintype "passive"))
    )
    (net (code "39") (name "/PWM_V_B") (class "Default")
      (node (ref "U6") (pin "8") (pinfunction "3Y_8") (pintype "passive"))
    )
    (net (code "40") (name "/PWM_V_HIGH") (class "Default")
      (node (ref "U1") (pin "42") (pinfunction "PA9_42") (pintype "passive"))
      (node (ref "U5") (pin "4") (pinfunction "2A_4") (pintype "passive"))
      (node (ref "U6") (pin "13") (pinfunction "4B_13") (pintype "passive"))
    )
    (net (code "41") (name "/PWM_V_LOW") (class "Default")
      (node (ref "U1") (pin "35") (pinfunction "PB14_35") (pintype "passive"))
      (node (ref "U5") (pin "5") (pinfunction "2B_5") (pintype "passive"))
      (node (ref "U6") (pin "9") (pinfunction "3A_9") (pintype "passive"))
    )
    (net (code "42") (name "/PWM_W_A") (class "Default")
      (node (ref "U7") (pin "3") (pinfunction "1Y_3") (pintype "passive"))
    )
    (net (code "43") (name "/PWM_W_B") (class "Default")
      (node (ref "U7") (pin "6") (pinfunction "2Y_6") (pintype "passive"))
    )
    (net (code "44") (name "/PWM_W_HIGH") (class "Default")
      (node (ref "U1") (pin "43") (pinfunction "PA10_43") (pintype "passive"))
      (node (ref "U5") (pin "10") (pinfunction "3A_10") (pintype "passive"))
      (node (ref "U7") (pin "1") (pinfunction "1A_1") (pintype "passive"))
    )
    (net (code "45") (name "/PWM_W_LOW") (class "Default")
      (node (ref "U1") (pin "36") (pinfunction "PB15_36") (pintype "passive"))
      (node (ref "U5") (pin "9") (pinfunction "3B_9") (pintype "passive"))
      (node (ref "U7") (pin "5") (pinfunction "2B_5") (pintype "passive"))
    )
    (net (code "46") (name "/RC_PWM") (class "Default")
      (node (ref "U1") (pin "58") (pinfunction "PB6_58") (pintype "passive"))
    )
    (net (code "47") (name "/RX") (class "Default")
      (node (ref "J_UART1") (pin "2") (pinfunction "2_2") (pintype "passive"))
    )
    (net (code "48") (name "/RX_SDA_NSS") (class "Default")
      (node (ref "U1") (pin "20") (pinfunction "PA4_20") (pintype "passive"))
      (node (ref "U1") (pin "30") (pinfunction "PB11_30") (pintype "passive"))
    )
    (net (code "49") (name "/SCK_ADC_EXT") (class "Default")
      (node (ref "U1") (pin "21") (pinfunction "PA5_21") (pintype "passive"))
    )
    (net (code "50") (name "/SWCLK") (class "Default")
      (node (ref "J1") (pin "2") (pinfunction "2_2") (pintype "passive"))
      (node (ref "U1") (pin "49") (pinfunction "PA14_49") (pintype "passive"))
    )
    (net (code "51") (name "/SWDIO") (class "Default")
      (node (ref "J1") (pin "4") (pinfunction "4_4") (pintype "passive"))
      (node (ref "U1") (pin "46") (pinfunction "PA13_46") (pintype "passive"))
    )
    (net (code "52") (name "/TEMP") (class "Default")
      (node (ref "U1") (pin "17") (pinfunction "PA3_17") (pintype "passive"))
    )
    (net (code "53") (name "/TEMP_MOTOR") (class "Default")
      (node (ref "U1") (pin "24") (pinfunction "PC4_24") (pintype "passive"))
    )
    (net (code "54") (name "/TX") (class "Default")
      (node (ref "J_UART1") (pin "3") (pinfunction "3_3") (pintype "passive"))
    )
    (net (code "55") (name "/TX_SCL_MOSI") (class "Default")
      (node (ref "U1") (pin "23") (pinfunction "PA7_23") (pintype "passive"))
      (node (ref "U1") (pin "29") (pinfunction "PB10_29") (pintype "passive"))
    )
    (net (code "56") (name "/USB_DM") (class "Default")
      (node (ref "R2") (pin "2") (pinfunction "2_2") (pintype "passive"))
      (node (ref "U1") (pin "44") (pinfunction "PA11_44") (pintype "passive"))
    )
    (net (code "57") (name "/USB_DP") (class "Default")
      (node (ref "R1") (pin "2") (pinfunction "2_2") (pintype "passive"))
      (node (ref "U1") (pin "45") (pinfunction "PA12_45") (pintype "passive"))
    )
    (net (code "58") (name "/VBUS") (class "Default")
      (node (ref "J_USB1") (pin "1") (pinfunction "1_1") (pintype "passive"))
      (node (ref "U2") (pin "5") (pinfunction "VBUS_5") (pintype "passive"))
    )
    (net (code "59") (name "/VCAP1") (class "Default")
      (node (ref "C17") (pin "2") (pinfunction "2_2") (pintype "passive"))
      (node (ref "U1") (pin "31") (pinfunction "VCAP_1_31") (pintype "passive"))
    )
    (net (code "60") (name "/VCAP2") (class "Default")
      (node (ref "C18") (pin "2") (pinfunction "2_2") (pintype "passive"))
      (node (ref "U1") (pin "47") (pinfunction "VCAP_2_47") (pintype "passive"))
    )
    (net (code "61") (name "/VSENSE") (class "Default")
      (node (ref "U1") (pin "11") (pinfunction "PC3_11") (pintype "passive"))
    )
    (net (code "62") (name "/VSENSE_U") (class "Default")
      (node (ref "U1") (pin "14") (pinfunction "PA0_WKUP_14") (pintype "passive"))
    )
    (net (code "63") (name "/VSENSE_V") (class "Default")
      (node (ref "U1") (pin "15") (pinfunction "PA1_15") (pintype "passive"))
    )
    (net (code "64") (name "/VSENSE_W") (class "Default")
      (node (ref "U1") (pin "16") (pinfunction "PA2_16") (pintype "passive"))
    )
    (net (code "65") (name "GND") (class "Default")
      (node (ref "C1") (pin "1") (pinfunction "1_1") (pintype "passive"))
      (node (ref "C10") (pin "1") (pinfunction "1_1") (pintype "passive"))
      (node (ref "C11") (pin "1") (pinfunction "1_1") (pintype "passive"))
      (node (ref "C12") (pin "1") (pinfunction "1_1") (pintype "passive"))
      (node (ref "C13") (pin "1") (pinfunction "1_1") (pintype "passive"))
      (node (ref "C14") (pin "1") (pinfunction "1_1") (pintype "passive"))
      (node (ref "C15") (pin "1") (pinfunction "1_1") (pintype "passive"))
      (node (ref "C16") (pin "1") (pinfunction "1_1") (pintype "passive"))
      (node (ref "C17") (pin "1") (pinfunction "1_1") (pintype "passive"))
      (node (ref "C18") (pin "1") (pinfunction "1_1") (pintype "passive"))
      (node (ref "C19") (pin "1") (pinfunction "1_1") (pintype "passive"))
      (node (ref "C2") (pin "1") (pinfunction "1_1") (pintype "passive"))
      (node (ref "C20") (pin "1") (pinfunction "1_1") (pintype "passive"))
      (node (ref "C21") (pin "2") (pinfunction "2_2") (pintype "passive"))
      (node (ref "C22") (pin "1") (pinfunction "1_1") (pintype "passive"))
      (node (ref "C23") (pin "1") (pinfunction "1_1") (pintype "passive"))
      (node (ref "C26") (pin "1") (pinfunction "1_1") (pintype "passive"))
      (node (ref "C27") (pin "1") (pinfunction "1_1") (pintype "passive"))
      (node (ref "C28") (pin "1") (pinfunction "1_1") (pintype "passive"))
      (node (ref "C3") (pin "1") (pinfunction "1_1") (pintype "passive"))
      (node (ref "C31") (pin "1") (pinfunction "1_1") (pintype "passive"))
      (node (ref "C34") (pin "1") (pinfunction "1_1") (pintype "passive"))
      (node (ref "C35") (pin "1") (pinfunction "1_1") (pintype "passive"))
      (node (ref "C4") (pin "1") (pinfunction "1_1") (pintype "passive"))
      (node (ref "C5") (pin "1") (pinfunction "1_1") (pintype "passive"))
      (node (ref "C6") (pin "1") (pinfunction "1_1") (pintype "passive"))
      (node (ref "C7") (pin "1") (pinfunction "1_1") (pintype "passive"))
      (node (ref "C8") (pin "1") (pinfunction "1_1") (pintype "passive"))
      (node (ref "C9") (pin "1") (pinfunction "1_1") (pintype "passive"))
      (node (ref "J1") (pin "3") (pinfunction "3_3") (pintype "passive"))
      (node (ref "J_CAN1") (pin "4") (pinfunction "4_4") (pintype "passive"))
      (node (ref "J_UART1") (pin "1") (pinfunction "1_1") (pintype "passive"))
      (node (ref "J_USB1") (pin "5") (pinfunction "5_5") (pintype "passive"))
      (node (ref "R14") (pin "2") (pinfunction "2_2") (pintype "passive"))
      (node (ref "R15") (pin "2") (pinfunction "2_2") (pintype "passive"))
      (node (ref "R24") (pin "2") (pinfunction "2_2") (pintype "passive"))
      (node (ref "R25") (pin "2") (pinfunction "2_2") (pintype "passive"))
      (node (ref "R38") (pin "2") (pinfunction "2_2") (pintype "passive"))
      (node (ref "R39") (pin "2") (pinfunction "2_2") (pintype "passive"))
      (node (ref "U1") (pin "13") (pinfunction "VDDA_13") (pintype "passive"))
      (node (ref "U1") (pin "18") (pinfunction "VSS_1_18") (pintype "passive"))
      (node (ref "U1") (pin "60") (pinfunction "BOOT0_60") (pintype "passive"))
      (node (ref "U1") (pin "63") (pinfunction "VSS_2_63") (pintype "passive"))
      (node (ref "U10") (pin "4") (pinfunction "GND_4") (pintype "passive"))
      (node (ref "U11") (pin "4") (pinfunction "GND_4") (pintype "passive"))
      (node (ref "U12") (pin "4") (pinfunction "V-_4") (pintype "passive"))
      (node (ref "U2") (pin "2") (pinfunction "GND_2") (pintype "passive"))
      (node (ref "U3") (pin "2") (pinfunction "GND_2") (pintype "passive"))
      (node (ref "U3") (pin "8") (pinfunction "S_8") (pintype "passive"))
      (node (ref "U4") (pin "4") (pinfunction "GND_4") (pintype "passive"))
      (node (ref "U5") (pin "7") (pinfunction "GND_7") (pintype "passive"))
      (node (ref "U6") (pin "7") (pinfunction "GND_7") (pintype "passive"))
      (node (ref "U7") (pin "7") (pinfunction "GND_7") (pintype "passive"))
      (node (ref "U8") (pin "4") (pinfunction "GND_4") (pintype "passive"))
      (node (ref "U9") (pin "4") (pinfunction "V-_4") (pintype "passive"))
      (node (ref "Y1") (pin "2") (pinfunction "GND_2") (pintype "power_in"))
      (node (ref "Y1") (pin "4") (pinfunction "GND_4") (pintype "power_in"))
    )
    (net (code "66") (name "Net-(C24-Pad1)") (class "Default")
      (node (ref "C24") (pin "1") (pinfunction "1_1") (pintype "passive"))
      (node (ref "R17") (pin "2") (pinfunction "2_2") (pintype "passive"))
      (node (ref "R19") (pin "1") (pinfunction "1_1") (pintype "passive"))
    )
    (net (code "67") (name "Net-(C24-Pad2)") (class "Default")
      (node (ref "C24") (pin "2") (pinfunction "2_2") (pintype "passive"))
      (node (ref "R10") (pin "1") (pinfunction "1_1") (pintype "passive"))
      (node (ref "R8") (pin "2") (pinfunction "2_2") (pintype "passive"))
    )
    (net (code "68") (name "Net-(C25-Pad1)") (class "Default")
      (node (ref "C25") (pin "1") (pinfunction "1_1") (pintype "passive"))
      (node (ref "R17") (pin "1") (pinfunction "1_1") (pintype "passive"))
      (node (ref "R18") (pin "2") (pinfunction "2_2") (pintype "passive"))
    )
    (net (code "69") (name "Net-(C25-Pad2)") (class "Default")
      (node (ref "C25") (pin "2") (pinfunction "2_2") (pintype "passive"))
      (node (ref "R8") (pin "1") (pinfunction "1_1") (pintype "passive"))
      (node (ref "R9") (pin "2") (pinfunction "2_2") (pintype "passive"))
    )
    (net (code "70") (name "Net-(C29-Pad1)") (class "Default")
      (node (ref "C29") (pin "1") (pinfunction "1_1") (pintype "passive"))
      (node (ref "R29") (pin "2") (pinfunction "2_2") (pintype "passive"))
      (node (ref "R31") (pin "1") (pinfunction "1_1") (pintype "passive"))
    )
    (net (code "71") (name "Net-(C29-Pad2)") (class "Default")
      (node (ref "C29") (pin "2") (pinfunction "2_2") (pintype "passive"))
      (node (ref "R22") (pin "2") (pinfunction "2_2") (pintype "passive"))
      (node (ref "R26") (pin "1") (pinfunction "1_1") (pintype "passive"))
    )
    (net (code "72") (name "Net-(C30-Pad1)") (class "Default")
      (node (ref "C30") (pin "1") (pinfunction "1_1") (pintype "passive"))
      (node (ref "R29") (pin "1") (pinfunction "1_1") (pintype "passive"))
      (node (ref "R30") (pin "2") (pinfunction "2_2") (pintype "passive"))
    )
    (net (code "73") (name "Net-(C30-Pad2)") (class "Default")
      (node (ref "C30") (pin "2") (pinfunction "2_2") (pintype "passive"))
      (node (ref "R22") (pin "1") (pinfunction "1_1") (pintype "passive"))
      (node (ref "R23") (pin "2") (pinfunction "2_2") (pintype "passive"))
    )
    (net (code "74") (name "Net-(C32-Pad1)") (class "Default")
      (node (ref "C32") (pin "1") (pinfunction "1_1") (pintype "passive"))
      (node (ref "R40") (pin "2") (pinfunction "2_2") (pintype "passive"))
      (node (ref "R42") (pin "1") (pinfunction "1_1") (pintype "passive"))
    )
    (net (code "75") (name "Net-(C32-Pad2)") (class "Default")
      (node (ref "C32") (pin "2") (pinfunction "2_2") (pintype "passive"))
      (node (ref "R32") (pin "2") (pinfunction "2_2") (pintype "passive"))
      (node (ref "R34") (pin "1") (pinfunction "1_1") (pintype "passive"))
    )
    (net (code "76") (name "Net-(C33-Pad1)") (class "Default")
      (node (ref "C33") (pin "1") (pinfunction "1_1") (pintype "passive"))
      (node (ref "R40") (pin "1") (pinfunction "1_1") (pintype "passive"))
      (node (ref "R41") (pin "2") (pinfunction "2_2") (pintype "passive"))
    )
    (net (code "77") (name "Net-(C33-Pad2)") (class "Default")
      (node (ref "C33") (pin "2") (pinfunction "2_2") (pintype "passive"))
      (node (ref "R32") (pin "1") (pinfunction "1_1") (pintype "passive"))
      (node (ref "R33") (pin "2") (pinfunction "2_2") (pintype "passive"))
    )
    (net (code "78") (name "Net-(DS1-PadA)") (class "Default")
      (node (ref "DS1") (pin "A") (pinfunction "A_A") (pintype "passive"))
      (node (ref "R3") (pin "1") (pinfunction "1_1") (pintype "passive"))
    )
    (net (code "79") (name "Net-(U2-I{slash}O1_1)") (class "Default")
      (node (ref "R1") (pin "1") (pinfunction "1_1") (pintype "passive"))
      (node (ref "U2") (pin "1") (pinfunction "I/O1_1_1") (pintype "passive"))
    )
    (net (code "80") (name "Net-(U2-I{slash}O2_1)") (class "Default")
      (node (ref "R2") (pin "1") (pinfunction "1_1") (pintype "passive"))
      (node (ref "U2") (pin "3") (pinfunction "I/O2_1_3") (pintype "passive"))
    )
    (net (code "81") (name "Net-(U4-~{Q})") (class "Default")
      (node (ref "DS1") (pin "C") (pinfunction "C_C") (pintype "passive"))
      (node (ref "U4") (pin "3") (pinfunction "~{Q}_3") (pintype "passive"))
    )
    (net (code "82") (name "Net-(U5-1Y)") (class "Default")
      (node (ref "U5") (pin "3") (pinfunction "1Y_3") (pintype "passive"))
      (node (ref "U6") (pin "2") (pinfunction "1B_2") (pintype "passive"))
      (node (ref "U6") (pin "4") (pinfunction "2A_4") (pintype "passive"))
    )
    (net (code "83") (name "Net-(U5-2Y)") (class "Default")
      (node (ref "U5") (pin "6") (pinfunction "2Y_6") (pintype "passive"))
      (node (ref "U6") (pin "10") (pinfunction "3B_10") (pintype "passive"))
      (node (ref "U6") (pin "12") (pinfunction "4A_12") (pintype "passive"))
    )
    (net (code "84") (name "Net-(U5-3Y)") (class "Default")
      (node (ref "U5") (pin "8") (pinfunction "3Y_8") (pintype "passive"))
      (node (ref "U7") (pin "2") (pinfunction "1B_2") (pintype "passive"))
      (node (ref "U7") (pin "4") (pinfunction "2A_4") (pintype "passive"))
    )
    (net (code "85") (name "Net-(U5-4A)") (class "Default")
      (node (ref "R4") (pin "1") (pinfunction "1_1") (pintype "passive"))
      (node (ref "U5") (pin "13") (pinfunction "4A_13") (pintype "passive"))
    )
    (net (code "86") (name "Net-(U8-1IN+)") (class "Default")
      (node (ref "C22") (pin "2") (pinfunction "2_2") (pintype "passive"))
      (node (ref "R11") (pin "2") (pinfunction "2_2") (pintype "passive"))
      (node (ref "R14") (pin "1") (pinfunction "1_1") (pintype "passive"))
      (node (ref "U8") (pin "3") (pinfunction "1IN+_3") (pintype "passive"))
    )
    (net (code "87") (name "Net-(U8-1IN-)") (class "Default")
      (node (ref "C20") (pin "2") (pinfunction "2_2") (pintype "passive"))
      (node (ref "R7") (pin "1") (pinfunction "1_1") (pintype "passive"))
      (node (ref "U8") (pin "2") (pinfunction "1IN-_2") (pintype "passive"))
      (node (ref "U8") (pin "5") (pinfunction "2IN+_5") (pintype "passive"))
    )
    (net (code "88") (name "Net-(U8-2IN-)") (class "Default")
      (node (ref "C23") (pin "2") (pinfunction "2_2") (pintype "passive"))
      (node (ref "R12") (pin "2") (pinfunction "2_2") (pintype "passive"))
      (node (ref "R15") (pin "1") (pinfunction "1_1") (pintype "passive"))
      (node (ref "U8") (pin "6") (pinfunction "2IN-_6") (pintype "passive"))
    )
    (net (code "89") (name "Net-(U9-+IN_A)") (class "Default")
      (node (ref "R18") (pin "1") (pinfunction "1_1") (pintype "passive"))
      (node (ref "U9") (pin "3") (pinfunction "+IN_A_3") (pintype "passive"))
    )
    (net (code "90") (name "Net-(U9-+IN_B)") (class "Default")
      (node (ref "R30") (pin "1") (pinfunction "1_1") (pintype "passive"))
      (node (ref "U9") (pin "5") (pinfunction "+IN_B_5") (pintype "passive"))
    )
    (net (code "91") (name "Net-(U9--IN_A)") (class "Default")
      (node (ref "R9") (pin "1") (pinfunction "1_1") (pintype "passive"))
      (node (ref "U9") (pin "2") (pinfunction "-IN_A_2") (pintype "passive"))
    )
    (net (code "92") (name "Net-(U9--IN_B)") (class "Default")
      (node (ref "R23") (pin "1") (pinfunction "1_1") (pintype "passive"))
      (node (ref "U9") (pin "6") (pinfunction "-IN_B_6") (pintype "passive"))
    )
    (net (code "93") (name "Net-(U9-OUT_A)") (class "Default")
      (node (ref "R7") (pin "2") (pinfunction "2_2") (pintype "passive"))
      (node (ref "U9") (pin "1") (pinfunction "OUT_A_1") (pintype "passive"))
    )
    (net (code "94") (name "Net-(U9-OUT_B)") (class "Default")
      (node (ref "R13") (pin "2") (pinfunction "2_2") (pintype "passive"))
      (node (ref "U9") (pin "7") (pinfunction "OUT_B_7") (pintype "passive"))
    )
    (net (code "95") (name "Net-(U10-1IN+)") (class "Default")
      (node (ref "C27") (pin "2") (pinfunction "2_2") (pintype "passive"))
      (node (ref "R20") (pin "2") (pinfunction "2_2") (pintype "passive"))
      (node (ref "R24") (pin "1") (pinfunction "1_1") (pintype "passive"))
      (node (ref "U10") (pin "3") (pinfunction "1IN+_3") (pintype "passive"))
    )
    (net (code "96") (name "Net-(U10-1IN-)") (class "Default")
      (node (ref "C26") (pin "2") (pinfunction "2_2") (pintype "passive"))
      (node (ref "R13") (pin "1") (pinfunction "1_1") (pintype "passive"))
      (node (ref "U10") (pin "2") (pinfunction "1IN-_2") (pintype "passive"))
      (node (ref "U10") (pin "5") (pinfunction "2IN+_5") (pintype "passive"))
    )
    (net (code "97") (name "Net-(U10-2IN-)") (class "Default")
      (node (ref "C28") (pin "2") (pinfunction "2_2") (pintype "passive"))
      (node (ref "R21") (pin "2") (pinfunction "2_2") (pintype "passive"))
      (node (ref "R25") (pin "1") (pinfunction "1_1") (pintype "passive"))
      (node (ref "U10") (pin "6") (pinfunction "2IN-_6") (pintype "passive"))
    )
    (net (code "98") (name "Net-(U11-1IN+)") (class "Default")
      (node (ref "C34") (pin "2") (pinfunction "2_2") (pintype "passive"))
      (node (ref "R35") (pin "2") (pinfunction "2_2") (pintype "passive"))
      (node (ref "R38") (pin "1") (pinfunction "1_1") (pintype "passive"))
      (node (ref "U11") (pin "3") (pinfunction "1IN+_3") (pintype "passive"))
    )
    (net (code "99") (name "Net-(U11-1IN-)") (class "Default")
      (node (ref "C31") (pin "2") (pinfunction "2_2") (pintype "passive"))
      (node (ref "R27") (pin "1") (pinfunction "1_1") (pintype "passive"))
      (node (ref "U11") (pin "2") (pinfunction "1IN-_2") (pintype "passive"))
      (node (ref "U11") (pin "5") (pinfunction "2IN+_5") (pintype "passive"))
    )
    (net (code "100") (name "Net-(U11-2IN-)") (class "Default")
      (node (ref "C35") (pin "2") (pinfunction "2_2") (pintype "passive"))
      (node (ref "R36") (pin "2") (pinfunction "2_2") (pintype "passive"))
      (node (ref "R39") (pin "1") (pinfunction "1_1") (pintype "passive"))
      (node (ref "U11") (pin "6") (pinfunction "2IN-_6") (pintype "passive"))
    )
    (net (code "101") (name "Net-(U12-+IN_A)") (class "Default")
      (node (ref "R41") (pin "1") (pinfunction "1_1") (pintype "passive"))
      (node (ref "U12") (pin "3") (pinfunction "+IN_A_3") (pintype "passive"))
    )
    (net (code "102") (name "Net-(U12--IN_A)") (class "Default")
      (node (ref "R33") (pin "1") (pinfunction "1_1") (pintype "passive"))
      (node (ref "U12") (pin "2") (pinfunction "-IN_A_2") (pintype "passive"))
    )
    (net (code "103") (name "Net-(U12-OUT_A)") (class "Default")
      (node (ref "R27") (pin "2") (pinfunction "2_2") (pintype "passive"))
      (node (ref "U12") (pin "1") (pinfunction "OUT_A_1") (pintype "passive"))
    )
    (net (code "104") (name "VDDA") (class "Default")
      (node (ref "C11") (pin "2") (pinfunction "2_2") (pintype "passive"))
      (node (ref "C12") (pin "2") (pinfunction "2_2") (pintype "passive"))
      (node (ref "C13") (pin "2") (pinfunction "2_2") (pintype "passive"))
      (node (ref "FL1") (pin "2") (pinfunction "2_2") (pintype "passive"))
      (node (ref "U1") (pin "12") (pinfunction "VSSA_12") (pintype "passive"))
    )
    (net (code "105") (name "unconnected-(J_USB1-Pad4)") (class "Default")
      (node (ref "J_USB1") (pin "4") (pinfunction "4_4") (pintype "passive+no_connect"))
    )
    (net (code "106") (name "unconnected-(J_USB1-SHIELD-PadSH1)") (class "Default")
      (node (ref "J_USB1") (pin "SH1") (pinfunction "SHIELD_SH1") (pintype "passive"))
    )
    (net (code "107") (name "unconnected-(J_USB1-SHIELD-PadSH2)") (class "Default")
      (node (ref "J_USB1") (pin "SH2") (pinfunction "SHIELD_SH2") (pintype "passive"))
    )
    (net (code "108") (name "unconnected-(U1-PA15-Pad50)") (class "Default")
      (node (ref "U1") (pin "50") (pinfunction "PA15_50") (pintype "passive"))
    )
    (net (code "109") (name "unconnected-(U1-PB2-Pad28)") (class "Default")
      (node (ref "U1") (pin "28") (pinfunction "PB2_28") (pintype "passive"))
    )
    (net (code "110") (name "unconnected-(U1-PB3-Pad55)") (class "Default")
      (node (ref "U1") (pin "55") (pinfunction "PB3_55") (pintype "passive"))
    )
    (net (code "111") (name "unconnected-(U1-PB5-Pad57)") (class "Default")
      (node (ref "U1") (pin "57") (pinfunction "PB5_57") (pintype "passive"))
    )
    (net (code "112") (name "unconnected-(U1-PB7-Pad59)") (class "Default")
      (node (ref "U1") (pin "59") (pinfunction "PB7_59") (pintype "passive"))
    )
    (net (code "113") (name "unconnected-(U1-PB12-Pad33)") (class "Default")
      (node (ref "U1") (pin "33") (pinfunction "PB12_33") (pintype "passive"))
    )
    (net (code "114") (name "unconnected-(U1-PC9-Pad40)") (class "Default")
      (node (ref "U1") (pin "40") (pinfunction "PC9_40") (pintype "passive"))
    )
    (net (code "115") (name "unconnected-(U1-PC10-Pad51)") (class "Default")
      (node (ref "U1") (pin "51") (pinfunction "PC10_51") (pintype "passive"))
    )
    (net (code "116") (name "unconnected-(U1-PC11-Pad52)") (class "Default")
      (node (ref "U1") (pin "52") (pinfunction "PC11_52") (pintype "passive"))
    )
    (net (code "117") (name "unconnected-(U1-PC12-Pad53)") (class "Default")
      (node (ref "U1") (pin "53") (pinfunction "PC12_53") (pintype "passive"))
    )
    (net (code "118") (name "unconnected-(U1-PC13-Pad2)") (class "Default")
      (node (ref "U1") (pin "2") (pinfunction "PC13_2") (pintype "passive"))
    )
    (net (code "119") (name "unconnected-(U1-PC14-Pad3)") (class "Default")
      (node (ref "U1") (pin "3") (pinfunction "PC14_3") (pintype "passive"))
    )
    (net (code "120") (name "unconnected-(U1-PC15-Pad4)") (class "Default")
      (node (ref "U1") (pin "4") (pinfunction "PC15_4") (pintype "passive"))
    )
    (net (code "121") (name "unconnected-(U1-PD2-Pad54)") (class "Default")
      (node (ref "U1") (pin "54") (pinfunction "PD2_54") (pintype "passive"))
    )
    (net (code "122") (name "unconnected-(U7-3A-Pad9)") (class "Default")
      (node (ref "U7") (pin "9") (pinfunction "3A_9") (pintype "passive+no_connect"))
    )
    (net (code "123") (name "unconnected-(U7-3B-Pad10)") (class "Default")
      (node (ref "U7") (pin "10") (pinfunction "3B_10") (pintype "passive+no_connect"))
    )
    (net (code "124") (name "unconnected-(U7-3Y-Pad8)") (class "Default")
      (node (ref "U7") (pin "8") (pinfunction "3Y_8") (pintype "passive+no_connect"))
    )
    (net (code "125") (name "unconnected-(U7-4A-Pad12)") (class "Default")
      (node (ref "U7") (pin "12") (pinfunction "4A_12") (pintype "passive+no_connect"))
    )
    (net (code "126") (name "unconnected-(U7-4B-Pad13)") (class "Default")
      (node (ref "U7") (pin "13") (pinfunction "4B_13") (pintype "passive+no_connect"))
    )
    (net (code "127") (name "unconnected-(U7-4Y-Pad11)") (class "Default")
      (node (ref "U7") (pin "11") (pinfunction "4Y_11") (pintype "passive+no_connect"))
    )
    (net (code "128") (name "unconnected-(U12-+IN_B-Pad5)") (class "Default")
      (node (ref "U12") (pin "5") (pinfunction "+IN_B_5") (pintype "passive"))
    )
    (net (code "129") (name "unconnected-(U12--IN_B-Pad6)") (class "Default")
      (node (ref "U12") (pin "6") (pinfunction "-IN_B_6") (pintype "passive"))
    )
    (net (code "130") (name "unconnected-(U12-OUT_B-Pad7)") (class "Default")
      (node (ref "U12") (pin "7") (pinfunction "OUT_B_7") (pintype "passive"))
    )
  )
)
